# PowerSupply.net
KiCad netlist of a schematic drawn in Altium Designer
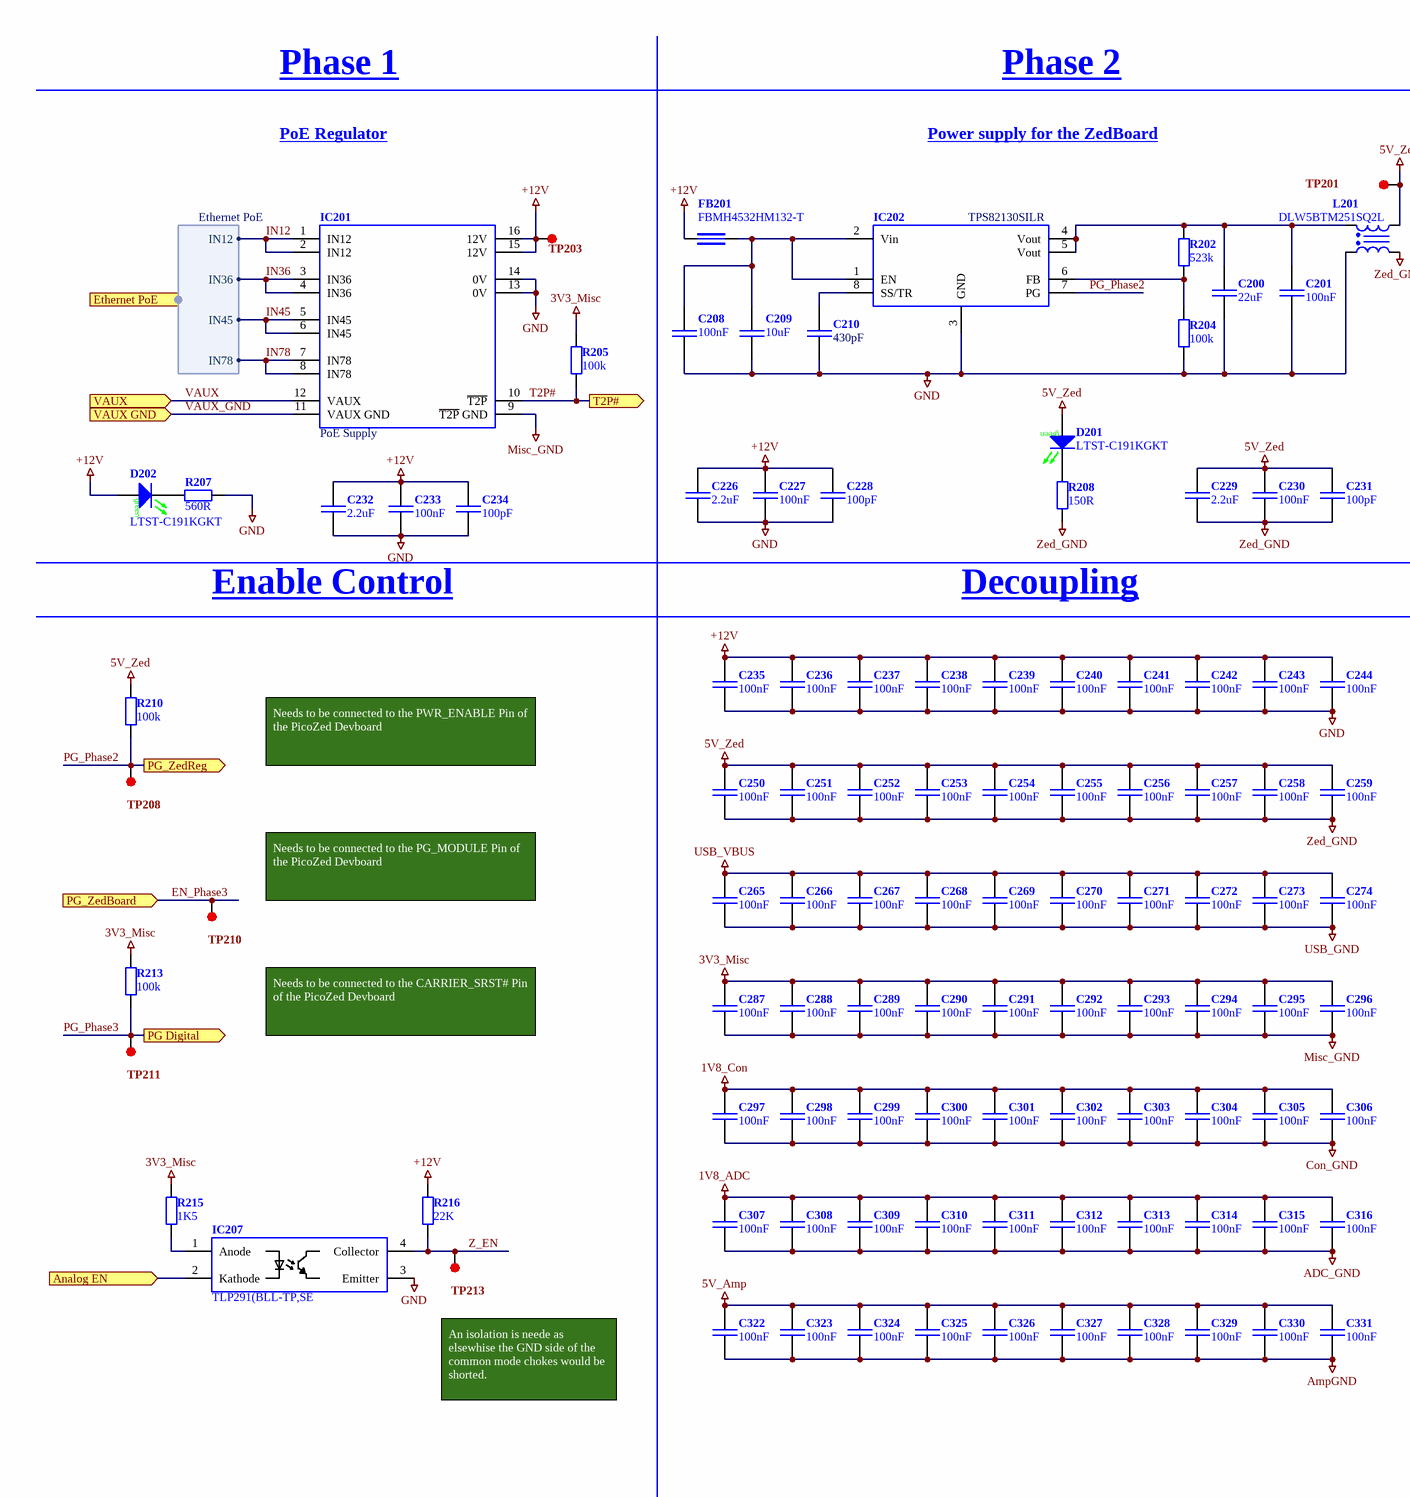
[diagram p0: PowerSupply.SchDoc, left]
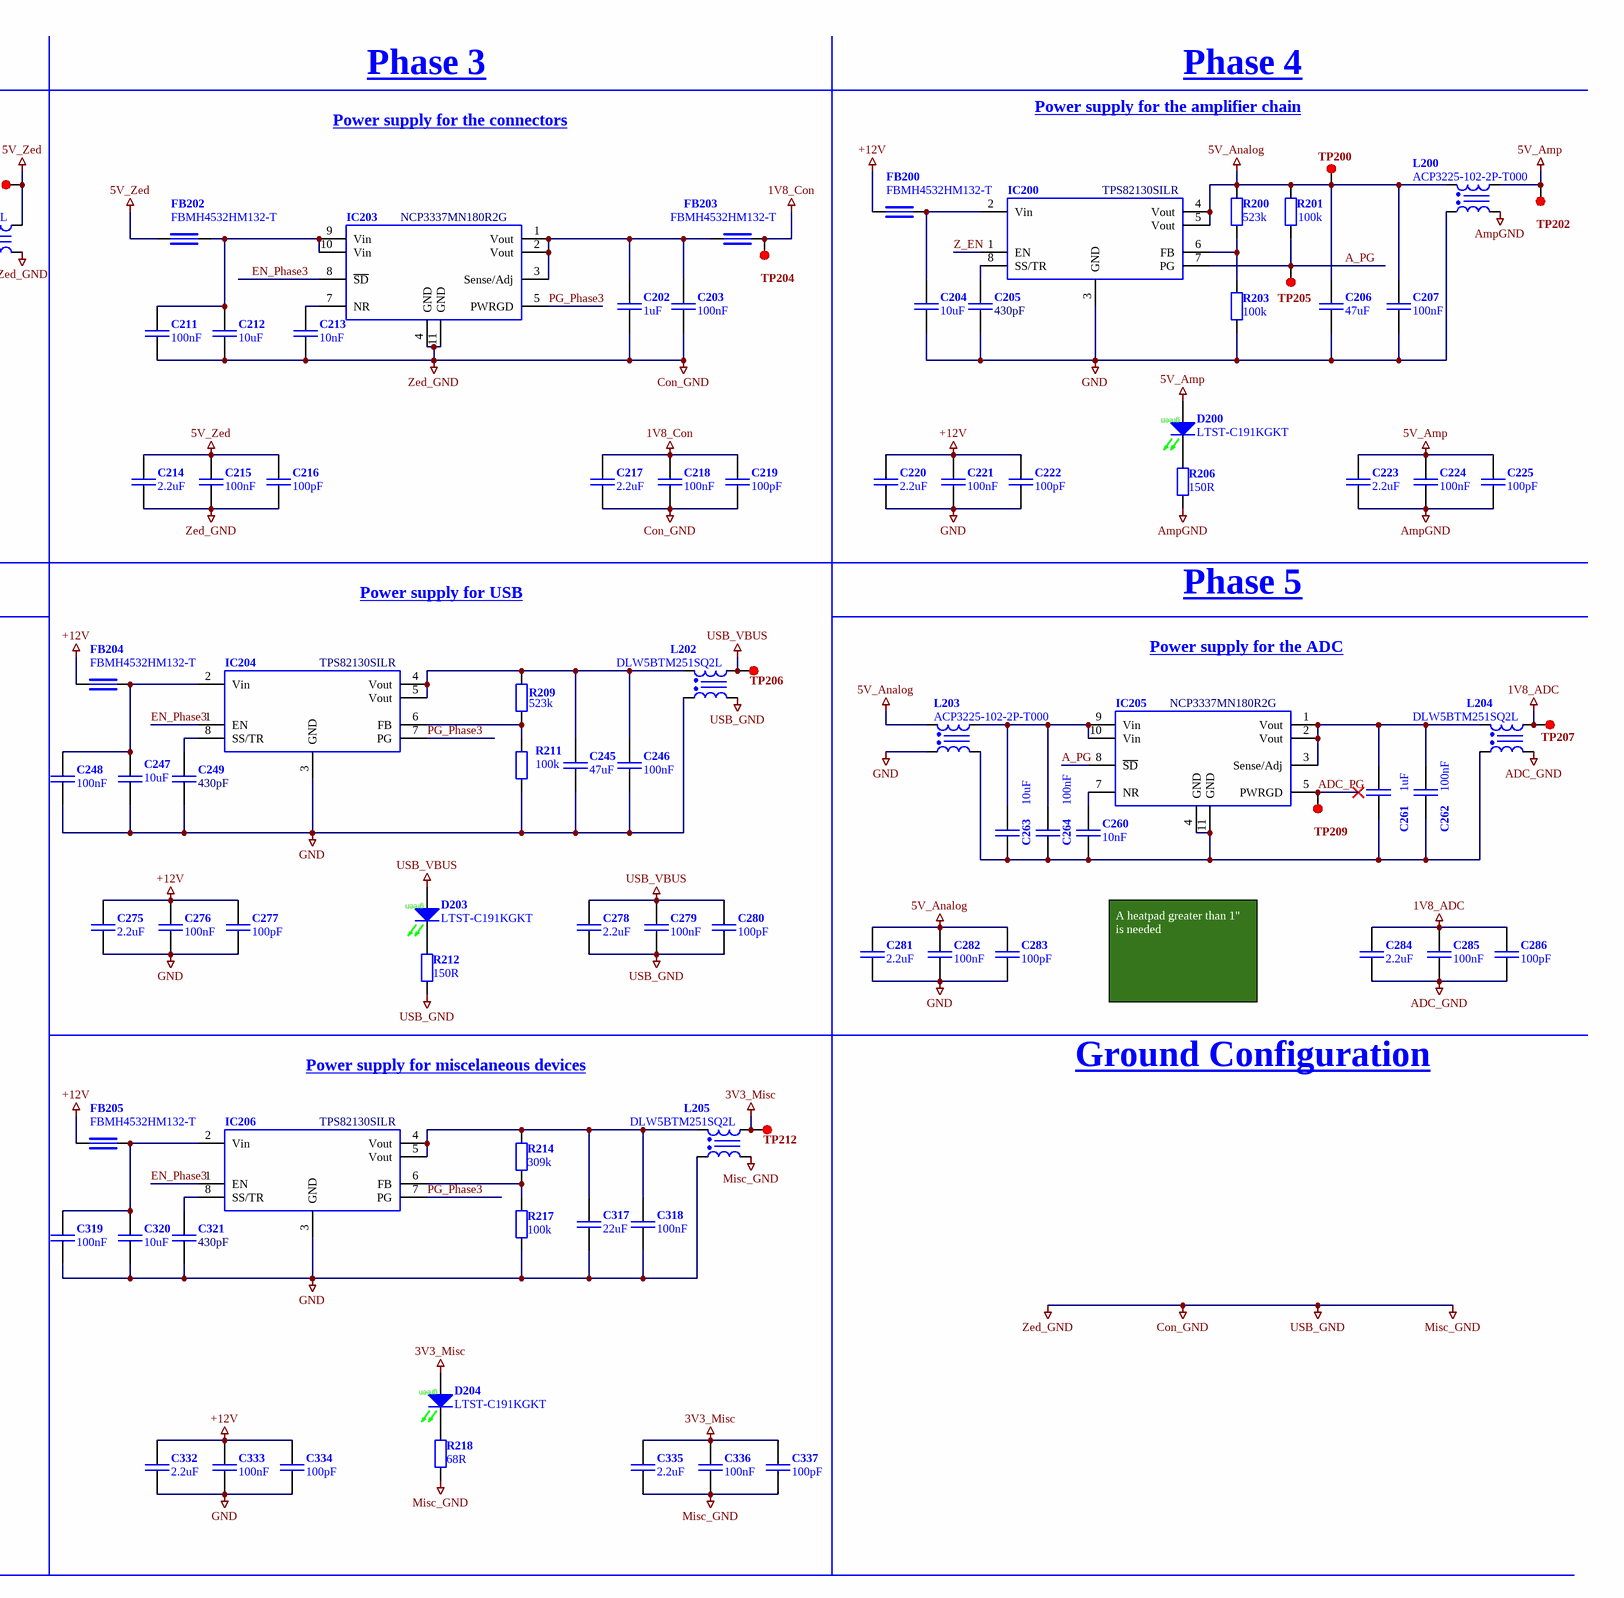
[diagram p1: PowerSupply.SchDoc, right]

(export (version "E")
  (design (tool "Eeschema 10.0.6"))
  (components
    (comp (ref "C200")
      (value "22uF")
      (footprint "PrometheusLib:C_0805_N [CAPC2013N IPC]")
      (libsource (lib "PrometheusLib") (part "C_GENERIC"))
    )
    (comp (ref "C201")
      (value "100nF")
      (footprint "PrometheusLib:C_0603_N [CAPC1608N IPC]")
      (libsource (lib "PrometheusLib") (part "C_GENERIC"))
    )
    (comp (ref "C202")
      (value "1uF")
      (footprint "PrometheusLib:C_0603_N [CAPC1608N IPC]")
      (libsource (lib "PrometheusLib") (part "C_GENERIC"))
    )
    (comp (ref "C203")
      (value "100nF")
      (footprint "PrometheusLib:C_0603_N [CAPC1608N IPC]")
      (libsource (lib "PrometheusLib") (part "C_GENERIC"))
    )
    (comp (ref "C204")
      (value "10uF")
      (footprint "PrometheusLib:C_1210_N [CAPC3225N IPC]")
      (libsource (lib "PrometheusLib") (part "C_GENERIC"))
    )
    (comp (ref "C205")
      (value "430pF")
      (footprint "PrometheusLib:C_0603_N [CAPC1608N IPC]")
      (libsource (lib "PrometheusLib") (part "C_GENERIC"))
    )
    (comp (ref "C206")
      (value "47uF")
      (footprint "PrometheusLib:C_0805_N [CAPC2013N IPC]")
      (libsource (lib "PrometheusLib") (part "C_GENERIC"))
    )
    (comp (ref "C207")
      (value "100nF")
      (footprint "PrometheusLib:C_0603_N [CAPC1608N IPC]")
      (libsource (lib "PrometheusLib") (part "C_GENERIC"))
    )
    (comp (ref "C208")
      (value "100nF")
      (footprint "PrometheusLib:C_0603_N [CAPC1608N IPC]")
      (libsource (lib "PrometheusLib") (part "C_GENERIC"))
    )
    (comp (ref "C209")
      (value "10uF")
      (footprint "PrometheusLib:C_1210_N [CAPC3225N IPC]")
      (libsource (lib "PrometheusLib") (part "C_GENERIC"))
    )
    (comp (ref "C210")
      (value "430pF")
      (footprint "PrometheusLib:C_0603_N [CAPC1608N IPC]")
      (libsource (lib "PrometheusLib") (part "C_GENERIC"))
    )
    (comp (ref "C211")
      (value "100nF")
      (footprint "PrometheusLib:C_0603_N [CAPC1608N IPC]")
      (libsource (lib "PrometheusLib") (part "C_GENERIC"))
    )
    (comp (ref "C212")
      (value "10uF")
      (footprint "PrometheusLib:C_0603_N [CAPC1608N IPC]")
      (libsource (lib "PrometheusLib") (part "C_GENERIC"))
    )
    (comp (ref "C213")
      (value "10nF")
      (footprint "PrometheusLib:C_0603_N [CAPC1608N IPC]")
      (libsource (lib "PrometheusLib") (part "C_GENERIC"))
    )
    (comp (ref "C214")
      (value "2.2uF")
      (footprint "PrometheusLib:C_1206_N [CAPC3216N IPC]")
      (libsource (lib "PrometheusLib") (part "C_GENERIC"))
    )
    (comp (ref "C215")
      (value "100nF")
      (footprint "PrometheusLib:C_0805_N [CAPC2013N IPC]")
      (libsource (lib "PrometheusLib") (part "C_GENERIC"))
    )
    (comp (ref "C216")
      (value "100pF")
      (footprint "PrometheusLib:C_0603_N [CAPC1608N IPC]")
      (libsource (lib "PrometheusLib") (part "C_GENERIC"))
    )
    (comp (ref "C217")
      (value "2.2uF")
      (footprint "PrometheusLib:C_1206_N [CAPC3216N IPC]")
      (libsource (lib "PrometheusLib") (part "C_GENERIC"))
    )
    (comp (ref "C218")
      (value "100nF")
      (footprint "PrometheusLib:C_0805_N [CAPC2013N IPC]")
      (libsource (lib "PrometheusLib") (part "C_GENERIC"))
    )
    (comp (ref "C219")
      (value "100pF")
      (footprint "PrometheusLib:C_0603_N [CAPC1608N IPC]")
      (libsource (lib "PrometheusLib") (part "C_GENERIC"))
    )
    (comp (ref "C220")
      (value "2.2uF")
      (footprint "PrometheusLib:C_1206_N [CAPC3216N IPC]")
      (libsource (lib "PrometheusLib") (part "C_GENERIC"))
    )
    (comp (ref "C221")
      (value "100nF")
      (footprint "PrometheusLib:C_0805_N [CAPC2013N IPC]")
      (libsource (lib "PrometheusLib") (part "C_GENERIC"))
    )
    (comp (ref "C222")
      (value "100pF")
      (footprint "PrometheusLib:C_0603_N [CAPC1608N IPC]")
      (libsource (lib "PrometheusLib") (part "C_GENERIC"))
    )
    (comp (ref "C223")
      (value "2.2uF")
      (footprint "PrometheusLib:C_1206_N [CAPC3216N IPC]")
      (libsource (lib "PrometheusLib") (part "C_GENERIC"))
    )
    (comp (ref "C224")
      (value "100nF")
      (footprint "PrometheusLib:C_0805_N [CAPC2013N IPC]")
      (libsource (lib "PrometheusLib") (part "C_GENERIC"))
    )
    (comp (ref "C225")
      (value "100pF")
      (footprint "PrometheusLib:C_0603_N [CAPC1608N IPC]")
      (libsource (lib "PrometheusLib") (part "C_GENERIC"))
    )
    (comp (ref "C226")
      (value "2.2uF")
      (footprint "PrometheusLib:C_1206_N [CAPC3216N IPC]")
      (libsource (lib "PrometheusLib") (part "C_GENERIC"))
    )
    (comp (ref "C227")
      (value "100nF")
      (footprint "PrometheusLib:C_0805_N [CAPC2013N IPC]")
      (libsource (lib "PrometheusLib") (part "C_GENERIC"))
    )
    (comp (ref "C228")
      (value "100pF")
      (footprint "PrometheusLib:C_0603_N [CAPC1608N IPC]")
      (libsource (lib "PrometheusLib") (part "C_GENERIC"))
    )
    (comp (ref "C229")
      (value "2.2uF")
      (footprint "PrometheusLib:C_1206_N [CAPC3216N IPC]")
      (libsource (lib "PrometheusLib") (part "C_GENERIC"))
    )
    (comp (ref "C230")
      (value "100nF")
      (footprint "PrometheusLib:C_0805_N [CAPC2013N IPC]")
      (libsource (lib "PrometheusLib") (part "C_GENERIC"))
    )
    (comp (ref "C231")
      (value "100pF")
      (footprint "PrometheusLib:C_0603_N [CAPC1608N IPC]")
      (libsource (lib "PrometheusLib") (part "C_GENERIC"))
    )
    (comp (ref "C232")
      (value "2.2uF")
      (footprint "PrometheusLib:C_1206_N [CAPC3216N IPC]")
      (libsource (lib "PrometheusLib") (part "C_GENERIC"))
    )
    (comp (ref "C233")
      (value "100nF")
      (footprint "PrometheusLib:C_0805_N [CAPC2013N IPC]")
      (libsource (lib "PrometheusLib") (part "C_GENERIC"))
    )
    (comp (ref "C234")
      (value "100pF")
      (footprint "PrometheusLib:C_0603_N [CAPC1608N IPC]")
      (libsource (lib "PrometheusLib") (part "C_GENERIC"))
    )
    (comp (ref "C235")
      (value "100nF")
      (footprint "PrometheusLib:C_0603_N [CAPC1608N IPC]")
      (libsource (lib "PrometheusLib") (part "C_GENERIC"))
    )
    (comp (ref "C236")
      (value "100nF")
      (footprint "PrometheusLib:C_0603_N [CAPC1608N IPC]")
      (libsource (lib "PrometheusLib") (part "C_GENERIC"))
    )
    (comp (ref "C237")
      (value "100nF")
      (footprint "PrometheusLib:C_0603_N [CAPC1608N IPC]")
      (libsource (lib "PrometheusLib") (part "C_GENERIC"))
    )
    (comp (ref "C238")
      (value "100nF")
      (footprint "PrometheusLib:C_0603_N [CAPC1608N IPC]")
      (libsource (lib "PrometheusLib") (part "C_GENERIC"))
    )
    (comp (ref "C239")
      (value "100nF")
      (footprint "PrometheusLib:C_0603_N [CAPC1608N IPC]")
      (libsource (lib "PrometheusLib") (part "C_GENERIC"))
    )
    (comp (ref "C240")
      (value "100nF")
      (footprint "PrometheusLib:C_0603_N [CAPC1608N IPC]")
      (libsource (lib "PrometheusLib") (part "C_GENERIC"))
    )
    (comp (ref "C241")
      (value "100nF")
      (footprint "PrometheusLib:C_0603_N [CAPC1608N IPC]")
      (libsource (lib "PrometheusLib") (part "C_GENERIC"))
    )
    (comp (ref "C242")
      (value "100nF")
      (footprint "PrometheusLib:C_0603_N [CAPC1608N IPC]")
      (libsource (lib "PrometheusLib") (part "C_GENERIC"))
    )
    (comp (ref "C243")
      (value "100nF")
      (footprint "PrometheusLib:C_0603_N [CAPC1608N IPC]")
      (libsource (lib "PrometheusLib") (part "C_GENERIC"))
    )
    (comp (ref "C244")
      (value "100nF")
      (footprint "PrometheusLib:C_0603_N [CAPC1608N IPC]")
      (libsource (lib "PrometheusLib") (part "C_GENERIC"))
    )
    (comp (ref "C245")
      (value "47uF")
      (footprint "PrometheusLib:C_0603_N [CAPC1608N IPC]")
      (libsource (lib "PrometheusLib") (part "C_GENERIC"))
    )
    (comp (ref "C246")
      (value "100nF")
      (footprint "PrometheusLib:C_0603_N [CAPC1608N IPC]")
      (libsource (lib "PrometheusLib") (part "C_GENERIC"))
    )
    (comp (ref "C247")
      (value "10uF")
      (footprint "PrometheusLib:C_1210_N [CAPC3225N IPC]")
      (libsource (lib "PrometheusLib") (part "C_GENERIC"))
    )
    (comp (ref "C248")
      (value "100nF")
      (footprint "PrometheusLib:C_0603_N [CAPC1608N IPC]")
      (libsource (lib "PrometheusLib") (part "C_GENERIC"))
    )
    (comp (ref "C249")
      (value "430pF")
      (footprint "PrometheusLib:C_0603_N [CAPC1608N IPC]")
      (libsource (lib "PrometheusLib") (part "C_GENERIC"))
    )
    (comp (ref "C250")
      (value "100nF")
      (footprint "PrometheusLib:C_0603_N [CAPC1608N IPC]")
      (libsource (lib "PrometheusLib") (part "C_GENERIC"))
    )
    (comp (ref "C251")
      (value "100nF")
      (footprint "PrometheusLib:C_0603_N [CAPC1608N IPC]")
      (libsource (lib "PrometheusLib") (part "C_GENERIC"))
    )
    (comp (ref "C252")
      (value "100nF")
      (footprint "PrometheusLib:C_0603_N [CAPC1608N IPC]")
      (libsource (lib "PrometheusLib") (part "C_GENERIC"))
    )
    (comp (ref "C253")
      (value "100nF")
      (footprint "PrometheusLib:C_0603_N [CAPC1608N IPC]")
      (libsource (lib "PrometheusLib") (part "C_GENERIC"))
    )
    (comp (ref "C254")
      (value "100nF")
      (footprint "PrometheusLib:C_0603_N [CAPC1608N IPC]")
      (libsource (lib "PrometheusLib") (part "C_GENERIC"))
    )
    (comp (ref "C255")
      (value "100nF")
      (footprint "PrometheusLib:C_0603_N [CAPC1608N IPC]")
      (libsource (lib "PrometheusLib") (part "C_GENERIC"))
    )
    (comp (ref "C256")
      (value "100nF")
      (footprint "PrometheusLib:C_0603_N [CAPC1608N IPC]")
      (libsource (lib "PrometheusLib") (part "C_GENERIC"))
    )
    (comp (ref "C257")
      (value "100nF")
      (footprint "PrometheusLib:C_0603_N [CAPC1608N IPC]")
      (libsource (lib "PrometheusLib") (part "C_GENERIC"))
    )
    (comp (ref "C258")
      (value "100nF")
      (footprint "PrometheusLib:C_0603_N [CAPC1608N IPC]")
      (libsource (lib "PrometheusLib") (part "C_GENERIC"))
    )
    (comp (ref "C259")
      (value "100nF")
      (footprint "PrometheusLib:C_0603_N [CAPC1608N IPC]")
      (libsource (lib "PrometheusLib") (part "C_GENERIC"))
    )
    (comp (ref "C260")
      (value "10nF")
      (footprint "PrometheusLib:C_0603_N [CAPC1608N IPC]")
      (libsource (lib "PrometheusLib") (part "C_GENERIC"))
    )
    (comp (ref "C261")
      (value "1uF")
      (footprint "PrometheusLib:C_0603_N [CAPC1608N IPC]")
      (libsource (lib "PrometheusLib") (part "C_GENERIC"))
    )
    (comp (ref "C262")
      (value "100nF")
      (footprint "PrometheusLib:C_0603_N [CAPC1608N IPC]")
      (libsource (lib "PrometheusLib") (part "C_GENERIC"))
    )
    (comp (ref "C263")
      (value "10uF")
      (footprint "PrometheusLib:C_0603_N [CAPC1608N IPC]")
      (libsource (lib "PrometheusLib") (part "C_GENERIC"))
    )
    (comp (ref "C264")
      (value "100nF")
      (footprint "PrometheusLib:C_0603_N [CAPC1608N IPC]")
      (libsource (lib "PrometheusLib") (part "C_GENERIC"))
    )
    (comp (ref "C265")
      (value "100nF")
      (footprint "PrometheusLib:C_0603_N [CAPC1608N IPC]")
      (libsource (lib "PrometheusLib") (part "C_GENERIC"))
    )
    (comp (ref "C266")
      (value "100nF")
      (footprint "PrometheusLib:C_0603_N [CAPC1608N IPC]")
      (libsource (lib "PrometheusLib") (part "C_GENERIC"))
    )
    (comp (ref "C267")
      (value "100nF")
      (footprint "PrometheusLib:C_0603_N [CAPC1608N IPC]")
      (libsource (lib "PrometheusLib") (part "C_GENERIC"))
    )
    (comp (ref "C268")
      (value "100nF")
      (footprint "PrometheusLib:C_0603_N [CAPC1608N IPC]")
      (libsource (lib "PrometheusLib") (part "C_GENERIC"))
    )
    (comp (ref "C269")
      (value "100nF")
      (footprint "PrometheusLib:C_0603_N [CAPC1608N IPC]")
      (libsource (lib "PrometheusLib") (part "C_GENERIC"))
    )
    (comp (ref "C270")
      (value "100nF")
      (footprint "PrometheusLib:C_0603_N [CAPC1608N IPC]")
      (libsource (lib "PrometheusLib") (part "C_GENERIC"))
    )
    (comp (ref "C271")
      (value "100nF")
      (footprint "PrometheusLib:C_0603_N [CAPC1608N IPC]")
      (libsource (lib "PrometheusLib") (part "C_GENERIC"))
    )
    (comp (ref "C272")
      (value "100nF")
      (footprint "PrometheusLib:C_0603_N [CAPC1608N IPC]")
      (libsource (lib "PrometheusLib") (part "C_GENERIC"))
    )
    (comp (ref "C273")
      (value "100nF")
      (footprint "PrometheusLib:C_0603_N [CAPC1608N IPC]")
      (libsource (lib "PrometheusLib") (part "C_GENERIC"))
    )
    (comp (ref "C274")
      (value "100nF")
      (footprint "PrometheusLib:C_0603_N [CAPC1608N IPC]")
      (libsource (lib "PrometheusLib") (part "C_GENERIC"))
    )
    (comp (ref "C275")
      (value "2.2uF")
      (footprint "PrometheusLib:C_1206_N [CAPC3216N IPC]")
      (libsource (lib "PrometheusLib") (part "C_GENERIC"))
    )
    (comp (ref "C276")
      (value "100nF")
      (footprint "PrometheusLib:C_0805_N [CAPC2013N IPC]")
      (libsource (lib "PrometheusLib") (part "C_GENERIC"))
    )
    (comp (ref "C277")
      (value "100pF")
      (footprint "PrometheusLib:C_0603_N [CAPC1608N IPC]")
      (libsource (lib "PrometheusLib") (part "C_GENERIC"))
    )
    (comp (ref "C278")
      (value "2.2uF")
      (footprint "PrometheusLib:C_1206_N [CAPC3216N IPC]")
      (libsource (lib "PrometheusLib") (part "C_GENERIC"))
    )
    (comp (ref "C279")
      (value "100nF")
      (footprint "PrometheusLib:C_0805_N [CAPC2013N IPC]")
      (libsource (lib "PrometheusLib") (part "C_GENERIC"))
    )
    (comp (ref "C280")
      (value "100pF")
      (footprint "PrometheusLib:C_0603_N [CAPC1608N IPC]")
      (libsource (lib "PrometheusLib") (part "C_GENERIC"))
    )
    (comp (ref "C281")
      (value "2.2uF")
      (footprint "PrometheusLib:C_1206_N [CAPC3216N IPC]")
      (libsource (lib "PrometheusLib") (part "C_GENERIC"))
    )
    (comp (ref "C282")
      (value "100nF")
      (footprint "PrometheusLib:C_0805_N [CAPC2013N IPC]")
      (libsource (lib "PrometheusLib") (part "C_GENERIC"))
    )
    (comp (ref "C283")
      (value "100pF")
      (footprint "PrometheusLib:C_0603_N [CAPC1608N IPC]")
      (libsource (lib "PrometheusLib") (part "C_GENERIC"))
    )
    (comp (ref "C284")
      (value "2.2uF")
      (footprint "PrometheusLib:C_1206_N [CAPC3216N IPC]")
      (libsource (lib "PrometheusLib") (part "C_GENERIC"))
    )
    (comp (ref "C285")
      (value "100nF")
      (footprint "PrometheusLib:C_0805_N [CAPC2013N IPC]")
      (libsource (lib "PrometheusLib") (part "C_GENERIC"))
    )
    (comp (ref "C286")
      (value "100pF")
      (footprint "PrometheusLib:C_0603_N [CAPC1608N IPC]")
      (libsource (lib "PrometheusLib") (part "C_GENERIC"))
    )
    (comp (ref "C287")
      (value "100nF")
      (footprint "PrometheusLib:C_0603_N [CAPC1608N IPC]")
      (libsource (lib "PrometheusLib") (part "C_GENERIC"))
    )
    (comp (ref "C288")
      (value "100nF")
      (footprint "PrometheusLib:C_0603_N [CAPC1608N IPC]")
      (libsource (lib "PrometheusLib") (part "C_GENERIC"))
    )
    (comp (ref "C289")
      (value "100nF")
      (footprint "PrometheusLib:C_0603_N [CAPC1608N IPC]")
      (libsource (lib "PrometheusLib") (part "C_GENERIC"))
    )
    (comp (ref "C290")
      (value "100nF")
      (footprint "PrometheusLib:C_0603_N [CAPC1608N IPC]")
      (libsource (lib "PrometheusLib") (part "C_GENERIC"))
    )
    (comp (ref "C291")
      (value "100nF")
      (footprint "PrometheusLib:C_0603_N [CAPC1608N IPC]")
      (libsource (lib "PrometheusLib") (part "C_GENERIC"))
    )
    (comp (ref "C292")
      (value "100nF")
      (footprint "PrometheusLib:C_0603_N [CAPC1608N IPC]")
      (libsource (lib "PrometheusLib") (part "C_GENERIC"))
    )
    (comp (ref "C293")
      (value "100nF")
      (footprint "PrometheusLib:C_0603_N [CAPC1608N IPC]")
      (libsource (lib "PrometheusLib") (part "C_GENERIC"))
    )
    (comp (ref "C294")
      (value "100nF")
      (footprint "PrometheusLib:C_0603_N [CAPC1608N IPC]")
      (libsource (lib "PrometheusLib") (part "C_GENERIC"))
    )
    (comp (ref "C295")
      (value "100nF")
      (footprint "PrometheusLib:C_0603_N [CAPC1608N IPC]")
      (libsource (lib "PrometheusLib") (part "C_GENERIC"))
    )
    (comp (ref "C296")
      (value "100nF")
      (footprint "PrometheusLib:C_0603_N [CAPC1608N IPC]")
      (libsource (lib "PrometheusLib") (part "C_GENERIC"))
    )
    (comp (ref "C297")
      (value "100nF")
      (footprint "PrometheusLib:C_0603_N [CAPC1608N IPC]")
      (libsource (lib "PrometheusLib") (part "C_GENERIC"))
    )
    (comp (ref "C298")
      (value "100nF")
      (footprint "PrometheusLib:C_0603_N [CAPC1608N IPC]")
      (libsource (lib "PrometheusLib") (part "C_GENERIC"))
    )
    (comp (ref "C299")
      (value "100nF")
      (footprint "PrometheusLib:C_0603_N [CAPC1608N IPC]")
      (libsource (lib "PrometheusLib") (part "C_GENERIC"))
    )
    (comp (ref "C300")
      (value "100nF")
      (footprint "PrometheusLib:C_0603_N [CAPC1608N IPC]")
      (libsource (lib "PrometheusLib") (part "C_GENERIC"))
    )
    (comp (ref "C301")
      (value "100nF")
      (footprint "PrometheusLib:C_0603_N [CAPC1608N IPC]")
      (libsource (lib "PrometheusLib") (part "C_GENERIC"))
    )
    (comp (ref "C302")
      (value "100nF")
      (footprint "PrometheusLib:C_0603_N [CAPC1608N IPC]")
      (libsource (lib "PrometheusLib") (part "C_GENERIC"))
    )
    (comp (ref "C303")
      (value "100nF")
      (footprint "PrometheusLib:C_0603_N [CAPC1608N IPC]")
      (libsource (lib "PrometheusLib") (part "C_GENERIC"))
    )
    (comp (ref "C304")
      (value "100nF")
      (footprint "PrometheusLib:C_0603_N [CAPC1608N IPC]")
      (libsource (lib "PrometheusLib") (part "C_GENERIC"))
    )
    (comp (ref "C305")
      (value "100nF")
      (footprint "PrometheusLib:C_0603_N [CAPC1608N IPC]")
      (libsource (lib "PrometheusLib") (part "C_GENERIC"))
    )
    (comp (ref "C306")
      (value "100nF")
      (footprint "PrometheusLib:C_0603_N [CAPC1608N IPC]")
      (libsource (lib "PrometheusLib") (part "C_GENERIC"))
    )
    (comp (ref "C307")
      (value "100nF")
      (footprint "PrometheusLib:C_0603_N [CAPC1608N IPC]")
      (libsource (lib "PrometheusLib") (part "C_GENERIC"))
    )
    (comp (ref "C308")
      (value "100nF")
      (footprint "PrometheusLib:C_0603_N [CAPC1608N IPC]")
      (libsource (lib "PrometheusLib") (part "C_GENERIC"))
    )
    (comp (ref "C309")
      (value "100nF")
      (footprint "PrometheusLib:C_0603_N [CAPC1608N IPC]")
      (libsource (lib "PrometheusLib") (part "C_GENERIC"))
    )
    (comp (ref "C310")
      (value "100nF")
      (footprint "PrometheusLib:C_0603_N [CAPC1608N IPC]")
      (libsource (lib "PrometheusLib") (part "C_GENERIC"))
    )
    (comp (ref "C311")
      (value "100nF")
      (footprint "PrometheusLib:C_0603_N [CAPC1608N IPC]")
      (libsource (lib "PrometheusLib") (part "C_GENERIC"))
    )
    (comp (ref "C312")
      (value "100nF")
      (footprint "PrometheusLib:C_0603_N [CAPC1608N IPC]")
      (libsource (lib "PrometheusLib") (part "C_GENERIC"))
    )
    (comp (ref "C313")
      (value "100nF")
      (footprint "PrometheusLib:C_0603_N [CAPC1608N IPC]")
      (libsource (lib "PrometheusLib") (part "C_GENERIC"))
    )
    (comp (ref "C314")
      (value "100nF")
      (footprint "PrometheusLib:C_0603_N [CAPC1608N IPC]")
      (libsource (lib "PrometheusLib") (part "C_GENERIC"))
    )
    (comp (ref "C315")
      (value "100nF")
      (footprint "PrometheusLib:C_0603_N [CAPC1608N IPC]")
      (libsource (lib "PrometheusLib") (part "C_GENERIC"))
    )
    (comp (ref "C316")
      (value "100nF")
      (footprint "PrometheusLib:C_0603_N [CAPC1608N IPC]")
      (libsource (lib "PrometheusLib") (part "C_GENERIC"))
    )
    (comp (ref "C317")
      (value "22uF")
      (footprint "PrometheusLib:C_0805_N [CAPC2013N IPC]")
      (libsource (lib "PrometheusLib") (part "C_GENERIC"))
    )
    (comp (ref "C318")
      (value "100nF")
      (footprint "PrometheusLib:C_0603_N [CAPC1608N IPC]")
      (libsource (lib "PrometheusLib") (part "C_GENERIC"))
    )
    (comp (ref "C319")
      (value "100nF")
      (footprint "PrometheusLib:C_0603_N [CAPC1608N IPC]")
      (libsource (lib "PrometheusLib") (part "C_GENERIC"))
    )
    (comp (ref "C320")
      (value "10uF")
      (footprint "PrometheusLib:C_1210_N [CAPC3225N IPC]")
      (libsource (lib "PrometheusLib") (part "C_GENERIC"))
    )
    (comp (ref "C321")
      (value "430pF")
      (footprint "PrometheusLib:C_0603_N [CAPC1608N IPC]")
      (libsource (lib "PrometheusLib") (part "C_GENERIC"))
    )
    (comp (ref "C322")
      (value "100nF")
      (footprint "PrometheusLib:C_0603_N [CAPC1608N IPC]")
      (libsource (lib "PrometheusLib") (part "C_GENERIC"))
    )
    (comp (ref "C323")
      (value "100nF")
      (footprint "PrometheusLib:C_0603_N [CAPC1608N IPC]")
      (libsource (lib "PrometheusLib") (part "C_GENERIC"))
    )
    (comp (ref "C324")
      (value "100nF")
      (footprint "PrometheusLib:C_0603_N [CAPC1608N IPC]")
      (libsource (lib "PrometheusLib") (part "C_GENERIC"))
    )
    (comp (ref "C325")
      (value "100nF")
      (footprint "PrometheusLib:C_0603_N [CAPC1608N IPC]")
      (libsource (lib "PrometheusLib") (part "C_GENERIC"))
    )
    (comp (ref "C326")
      (value "100nF")
      (footprint "PrometheusLib:C_0603_N [CAPC1608N IPC]")
      (libsource (lib "PrometheusLib") (part "C_GENERIC"))
    )
    (comp (ref "C327")
      (value "100nF")
      (footprint "PrometheusLib:C_0603_N [CAPC1608N IPC]")
      (libsource (lib "PrometheusLib") (part "C_GENERIC"))
    )
    (comp (ref "C328")
      (value "100nF")
      (footprint "PrometheusLib:C_0603_N [CAPC1608N IPC]")
      (libsource (lib "PrometheusLib") (part "C_GENERIC"))
    )
    (comp (ref "C329")
      (value "100nF")
      (footprint "PrometheusLib:C_0603_N [CAPC1608N IPC]")
      (libsource (lib "PrometheusLib") (part "C_GENERIC"))
    )
    (comp (ref "C330")
      (value "100nF")
      (footprint "PrometheusLib:C_0603_N [CAPC1608N IPC]")
      (libsource (lib "PrometheusLib") (part "C_GENERIC"))
    )
    (comp (ref "C331")
      (value "100nF")
      (footprint "PrometheusLib:C_0603_N [CAPC1608N IPC]")
      (libsource (lib "PrometheusLib") (part "C_GENERIC"))
    )
    (comp (ref "C332")
      (value "2.2uF")
      (footprint "PrometheusLib:C_1206_N [CAPC3216N IPC]")
      (libsource (lib "PrometheusLib") (part "C_GENERIC"))
    )
    (comp (ref "C333")
      (value "100nF")
      (footprint "PrometheusLib:C_0805_N [CAPC2013N IPC]")
      (libsource (lib "PrometheusLib") (part "C_GENERIC"))
    )
    (comp (ref "C334")
      (value "100pF")
      (footprint "PrometheusLib:C_0603_N [CAPC1608N IPC]")
      (libsource (lib "PrometheusLib") (part "C_GENERIC"))
    )
    (comp (ref "C335")
      (value "2.2uF")
      (footprint "PrometheusLib:C_1206_N [CAPC3216N IPC]")
      (libsource (lib "PrometheusLib") (part "C_GENERIC"))
    )
    (comp (ref "C336")
      (value "100nF")
      (footprint "PrometheusLib:C_0805_N [CAPC2013N IPC]")
      (libsource (lib "PrometheusLib") (part "C_GENERIC"))
    )
    (comp (ref "C337")
      (value "100pF")
      (footprint "PrometheusLib:C_0603_N [CAPC1608N IPC]")
      (libsource (lib "PrometheusLib") (part "C_GENERIC"))
    )
    (comp (ref "D200")
      (value "LTST-C191KGKT")
      (footprint "PrometheusLib:LED_0603-GREEN_N_AK")
      (libsource (lib "PrometheusLib") (part "LED_GREEN_GENERIC"))
    )
    (comp (ref "D201")
      (value "LTST-C191KGKT")
      (footprint "PrometheusLib:LED_0603-GREEN_N_AK")
      (libsource (lib "PrometheusLib") (part "LED_GREEN_GENERIC"))
    )
    (comp (ref "D202")
      (value "LTST-C191KGKT")
      (footprint "PrometheusLib:LED_0603-GREEN_N_AK")
      (libsource (lib "PrometheusLib") (part "LED_GREEN_GENERIC"))
    )
    (comp (ref "D203")
      (value "LTST-C191KGKT")
      (footprint "PrometheusLib:LED_0603-GREEN_N_AK")
      (libsource (lib "PrometheusLib") (part "LED_GREEN_GENERIC"))
    )
    (comp (ref "D204")
      (value "LTST-C191KGKT")
      (footprint "PrometheusLib:LED_0603-GREEN_N_AK")
      (libsource (lib "PrometheusLib") (part "LED_GREEN_GENERIC"))
    )
    (comp (ref "FB200")
      (value "FBMH4532HM132-T")
      (footprint "L_1812_N [INDC4532X25N IPC]")
      (description "1,3 kOHM @ 100 MHz\r\n3 A\r\n60 mOHM")
      (libsource (lib "PrometheusLib") (part "FB_FBMH4532HM132-T"))
    )
    (comp (ref "FB201")
      (value "FBMH4532HM132-T")
      (footprint "L_1812_N [INDC4532X25N IPC]")
      (description "1,3 kOHM @ 100 MHz\r\n3 A\r\n60 mOHM")
      (libsource (lib "PrometheusLib") (part "FB_FBMH4532HM132-T"))
    )
    (comp (ref "FB202")
      (value "FBMH4532HM132-T")
      (footprint "L_1812_N [INDC4532X25N IPC]")
      (description "1,3 kOHM @ 100 MHz\r\n3 A\r\n60 mOHM")
      (libsource (lib "PrometheusLib") (part "FB_FBMH4532HM132-T"))
    )
    (comp (ref "FB203")
      (value "FBMH4532HM132-T")
      (footprint "L_1812_N [INDC4532X25N IPC]")
      (description "1,3 kOHM @ 100 MHz\r\n3 A\r\n60 mOHM")
      (libsource (lib "PrometheusLib") (part "FB_FBMH4532HM132-T"))
    )
    (comp (ref "FB204")
      (value "FBMH4532HM132-T")
      (footprint "L_1812_N [INDC4532X25N IPC]")
      (description "1,3 kOHM @ 100 MHz\r\n3 A\r\n60 mOHM")
      (libsource (lib "PrometheusLib") (part "FB_FBMH4532HM132-T"))
    )
    (comp (ref "FB205")
      (value "FBMH4532HM132-T")
      (footprint "L_1812_N [INDC4532X25N IPC]")
      (description "1,3 kOHM @ 100 MHz\r\n3 A\r\n60 mOHM")
      (libsource (lib "PrometheusLib") (part "FB_FBMH4532HM132-T"))
    )
    (comp (ref "IC200")
      (value "TPS82130SILR")
      (footprint "SIL0008D")
      (description "Step-Down DC/DC\r\nVin = 4 V to 17 V\r\nVout = 0.9 V to 6 V Adjustable\r\nIout = 3 A")
      (libsource (lib "PrometheusLib") (part "SREG_TPS82130SILR"))
    )
    (comp (ref "IC201")
      (value "PoE Supply")
      (footprint "SREG_PoE_PowerSupply Prometheus")
      (libsource (lib "PrometheusLib") (part "SREG_PoE_PowerSupply"))
    )
    (comp (ref "IC202")
      (value "TPS82130SILR")
      (footprint "SIL0008D")
      (description "Step-Down DC/DC\r\nVin = 4 V to 17 V\r\nVout = 0.9 V to 6 V Adjustable\r\nIout = 3 A")
      (libsource (lib "PrometheusLib") (part "SREG_TPS82130SILR"))
    )
    (comp (ref "IC203")
      (value "NCP3337MN180R2G")
      (footprint "SON50P300X100_HS-11N")
      (description "LDO\r\nVin max. 16 V\r\nVout 1V8")
      (libsource (lib "PrometheusLib") (part "LDO_NCP3337"))
    )
    (comp (ref "IC204")
      (value "TPS82130SILR")
      (footprint "SIL0008D")
      (description "Step-Down DC/DC\r\nVin = 4 V to 17 V\r\nVout = 0.9 V to 6 V Adjustable\r\nIout = 3 A")
      (libsource (lib "PrometheusLib") (part "SREG_TPS82130SILR"))
    )
    (comp (ref "IC205")
      (value "NCP3337MN180R2G")
      (footprint "SON50P300X100_HS-11N")
      (description "LDO\r\nVin max. 16 V\r\nVout 1V8")
      (libsource (lib "PrometheusLib") (part "LDO_NCP3337"))
    )
    (comp (ref "IC206")
      (value "TPS82130SILR")
      (footprint "SIL0008D")
      (description "Step-Down DC/DC\r\nVin = 4 V to 17 V\r\nVout = 0.9 V to 6 V Adjustable\r\nIout = 3 A")
      (libsource (lib "PrometheusLib") (part "SREG_TPS82130SILR"))
    )
    (comp (ref "IC207")
      (value "TLP291(BLL-TP,SE")
      (footprint "SOP127P700X220-4N")
      (description "Opto-Isolator\r\nmin. VCE = 80 V\r\nmin. Current Transfer Ratio = 200 % @ 5 mA")
      (libsource (lib "PrometheusLib") (part "IC_TLP291(BLL-TP,SE"))
    )
    (comp (ref "L200")
      (value "ACP3225-102-2P-T000")
      (footprint "L_ACP3225-102-2P-T000")
      (libsource (lib "PrometheusLib") (part "L_COMMONMODE_CHOKE_744282010_1"))
    )
    (comp (ref "L201")
      (value "DLW5BTM251SQ2L")
      (footprint "L_COMMON_DLW5BTM251SQ2L Prometheus")
      (description "250 OHM @ 100 MHz\r\nI max. 5A\r\nDCR max. 20 mOHM\r\nVDC max. 50 V")
      (libsource (lib "PrometheusLib") (part "L_COMMONMODE_CHOKE_DLW5BTM251SQ2L"))
    )
    (comp (ref "L202")
      (value "DLW5BTM251SQ2L")
      (footprint "L_COMMON_DLW5BTM251SQ2L Prometheus")
      (description "250 OHM @ 100 MHz\r\nI max. 5A\r\nDCR max. 20 mOHM\r\nVDC max. 50 V")
      (libsource (lib "PrometheusLib") (part "L_COMMONMODE_CHOKE_DLW5BTM251SQ2L"))
    )
    (comp (ref "L203")
      (value "ACP3225-102-2P-T000")
      (footprint "L_ACP3225-102-2P-T000")
      (libsource (lib "PrometheusLib") (part "L_COMMONMODE_CHOKE_744282010_1"))
    )
    (comp (ref "L204")
      (value "DLW5BTM251SQ2L")
      (footprint "L_COMMON_DLW5BTM251SQ2L Prometheus")
      (description "250 OHM @ 100 MHz\r\nI max. 5A\r\nDCR max. 20 mOHM\r\nVDC max. 50 V")
      (libsource (lib "PrometheusLib") (part "L_COMMONMODE_CHOKE_DLW5BTM251SQ2L"))
    )
    (comp (ref "L205")
      (value "DLW5BTM251SQ2L")
      (footprint "L_COMMON_DLW5BTM251SQ2L Prometheus")
      (description "250 OHM @ 100 MHz\r\nI max. 5A\r\nDCR max. 20 mOHM\r\nVDC max. 50 V")
      (libsource (lib "PrometheusLib") (part "L_COMMONMODE_CHOKE_DLW5BTM251SQ2L"))
    )
    (comp (ref "R200")
      (value "523k")
      (footprint "PrometheusLib:R_0603_N [RESC1608N IPC]")
      (libsource (lib "PrometheusLib") (part "R_GENERIC_DIN"))
    )
    (comp (ref "R201")
      (value "100k")
      (footprint "PrometheusLib:R_0603_N [RESC1608N IPC]")
      (libsource (lib "PrometheusLib") (part "R_GENERIC_DIN"))
    )
    (comp (ref "R202")
      (value "523k")
      (footprint "PrometheusLib:R_0603_N [RESC1608N IPC]")
      (libsource (lib "PrometheusLib") (part "R_GENERIC_DIN"))
    )
    (comp (ref "R203")
      (value "100k")
      (footprint "PrometheusLib:R_0603_N [RESC1608N IPC]")
      (libsource (lib "PrometheusLib") (part "R_GENERIC_DIN"))
    )
    (comp (ref "R204")
      (value "100k")
      (footprint "PrometheusLib:R_0603_N [RESC1608N IPC]")
      (libsource (lib "PrometheusLib") (part "R_GENERIC_DIN"))
    )
    (comp (ref "R205")
      (value "100k")
      (footprint "PrometheusLib:R_0603_N [RESC1608N IPC]")
      (libsource (lib "PrometheusLib") (part "R_GENERIC_DIN"))
    )
    (comp (ref "R206")
      (value "150R")
      (footprint "PrometheusLib:R_0603_N [RESC1608N IPC]")
      (libsource (lib "PrometheusLib") (part "R_GENERIC_DIN"))
    )
    (comp (ref "R207")
      (value "560R")
      (footprint "PrometheusLib:R_0603_N [RESC1608N IPC]")
      (libsource (lib "") (part "R_GENERIC_DIN_2"))
    )
    (comp (ref "R208")
      (value "150R")
      (footprint "PrometheusLib:R_0603_N [RESC1608N IPC]")
      (libsource (lib "PrometheusLib") (part "R_GENERIC_DIN"))
    )
    (comp (ref "R209")
      (value "523k")
      (footprint "PrometheusLib:R_0603_N [RESC1608N IPC]")
      (libsource (lib "PrometheusLib") (part "R_GENERIC_DIN"))
    )
    (comp (ref "R210")
      (value "100k")
      (footprint "PrometheusLib:R_0603_N [RESC1608N IPC]")
      (libsource (lib "PrometheusLib") (part "R_GENERIC_DIN"))
    )
    (comp (ref "R211")
      (value "100k")
      (footprint "PrometheusLib:R_0603_N [RESC1608N IPC]")
      (libsource (lib "PrometheusLib") (part "R_GENERIC_DIN"))
    )
    (comp (ref "R212")
      (value "150R")
      (footprint "PrometheusLib:R_0603_N [RESC1608N IPC]")
      (libsource (lib "PrometheusLib") (part "R_GENERIC_DIN"))
    )
    (comp (ref "R213")
      (value "100k")
      (footprint "PrometheusLib:R_0603_N [RESC1608N IPC]")
      (libsource (lib "PrometheusLib") (part "R_GENERIC_DIN"))
    )
    (comp (ref "R214")
      (value "309k")
      (footprint "PrometheusLib:R_0603_N [RESC1608N IPC]")
      (libsource (lib "PrometheusLib") (part "R_GENERIC_DIN"))
    )
    (comp (ref "R215")
      (value "1K5")
      (footprint "PrometheusLib:R_0603_N [RESC1608N IPC]")
      (libsource (lib "") (part "R_GENERIC_DIN_1"))
    )
    (comp (ref "R216")
      (value "22K")
      (footprint "PrometheusLib:R_0603_N [RESC1608N IPC]")
      (libsource (lib "") (part "R_GENERIC_DIN_1"))
    )
    (comp (ref "R217")
      (value "100k")
      (footprint "PrometheusLib:R_0603_N [RESC1608N IPC]")
      (libsource (lib "PrometheusLib") (part "R_GENERIC_DIN"))
    )
    (comp (ref "R218")
      (value "68R")
      (footprint "PrometheusLib:R_0603_N [RESC1608N IPC]")
      (libsource (lib "PrometheusLib") (part "R_GENERIC_DIN"))
    )
    (comp (ref "TP200")
      (value "TP_GENERIC")
      (footprint "PrometheusLib:TP_0.8_P100T")
      (description "Needle Test Point")
      (libsource (lib "PrometheusLib") (part "TP_GENERIC"))
    )
    (comp (ref "TP201")
      (value "TP_GENERIC")
      (footprint "PrometheusLib:TP_0.8_P100T")
      (description "Needle Test Point")
      (libsource (lib "PrometheusLib") (part "TP_GENERIC"))
    )
    (comp (ref "TP202")
      (value "TP_GENERIC")
      (footprint "PrometheusLib:TP_0.8_P100T")
      (description "Needle Test Point")
      (libsource (lib "PrometheusLib") (part "TP_GENERIC"))
    )
    (comp (ref "TP203")
      (value "TP_GENERIC")
      (footprint "PrometheusLib:TP_0.8_P100T")
      (description "Needle Test Point")
      (libsource (lib "PrometheusLib") (part "TP_GENERIC"))
    )
    (comp (ref "TP204")
      (value "TP_GENERIC")
      (footprint "PrometheusLib:TP_0.8_P100T")
      (description "Needle Test Point")
      (libsource (lib "PrometheusLib") (part "TP_GENERIC"))
    )
    (comp (ref "TP205")
      (value "TP_GENERIC")
      (footprint "PrometheusLib:TP_0.8_P100T")
      (description "Needle Test Point")
      (libsource (lib "PrometheusLib") (part "TP_GENERIC"))
    )
    (comp (ref "TP206")
      (value "TP_GENERIC")
      (footprint "PrometheusLib:TP_0.8_P100T")
      (description "Needle Test Point")
      (libsource (lib "PrometheusLib") (part "TP_GENERIC"))
    )
    (comp (ref "TP207")
      (value "TP_GENERIC")
      (footprint "PrometheusLib:TP_0.8_P100T")
      (description "Needle Test Point")
      (libsource (lib "PrometheusLib") (part "TP_GENERIC"))
    )
    (comp (ref "TP208")
      (value "TP_GENERIC")
      (footprint "PrometheusLib:TP_0.8_P100T")
      (description "Needle Test Point")
      (libsource (lib "PrometheusLib") (part "TP_GENERIC"))
    )
    (comp (ref "TP209")
      (value "TP_GENERIC")
      (footprint "PrometheusLib:TP_0.8_P100T")
      (description "Needle Test Point")
      (libsource (lib "PrometheusLib") (part "TP_GENERIC"))
    )
    (comp (ref "TP210")
      (value "TP_GENERIC")
      (footprint "PrometheusLib:TP_0.8_P100T")
      (description "Needle Test Point")
      (libsource (lib "PrometheusLib") (part "TP_GENERIC"))
    )
    (comp (ref "TP211")
      (value "TP_GENERIC")
      (footprint "PrometheusLib:TP_0.8_P100T")
      (description "Needle Test Point")
      (libsource (lib "PrometheusLib") (part "TP_GENERIC"))
    )
    (comp (ref "TP212")
      (value "TP_GENERIC")
      (footprint "PrometheusLib:TP_0.8_P100T")
      (description "Needle Test Point")
      (libsource (lib "PrometheusLib") (part "TP_GENERIC"))
    )
    (comp (ref "TP213")
      (value "TP_GENERIC")
      (footprint "PrometheusLib:TP_0.8_P100T")
      (description "Needle Test Point")
      (libsource (lib "PrometheusLib") (part "TP_GENERIC"))
    )
  )
  (nets
    (net (code "3") (name "+12V") (class "Default")
      (node (ref "C220") (pin "1") (pintype "passive"))
      (node (ref "C221") (pin "1") (pintype "passive"))
      (node (ref "C222") (pin "1") (pintype "passive"))
      (node (ref "C226") (pin "1") (pintype "passive"))
      (node (ref "C227") (pin "1") (pintype "passive"))
      (node (ref "C228") (pin "1") (pintype "passive"))
      (node (ref "C232") (pin "1") (pintype "passive"))
      (node (ref "C233") (pin "1") (pintype "passive"))
      (node (ref "C234") (pin "1") (pintype "passive"))
      (node (ref "C235") (pin "1") (pintype "passive"))
      (node (ref "C236") (pin "1") (pintype "passive"))
      (node (ref "C237") (pin "1") (pintype "passive"))
      (node (ref "C238") (pin "1") (pintype "passive"))
      (node (ref "C239") (pin "1") (pintype "passive"))
      (node (ref "C240") (pin "1") (pintype "passive"))
      (node (ref "C241") (pin "1") (pintype "passive"))
      (node (ref "C242") (pin "1") (pintype "passive"))
      (node (ref "C243") (pin "1") (pintype "passive"))
      (node (ref "C244") (pin "1") (pintype "passive"))
      (node (ref "C275") (pin "1") (pintype "passive"))
      (node (ref "C276") (pin "1") (pintype "passive"))
      (node (ref "C277") (pin "1") (pintype "passive"))
      (node (ref "C332") (pin "1") (pintype "passive"))
      (node (ref "C333") (pin "1") (pintype "passive"))
      (node (ref "C334") (pin "1") (pintype "passive"))
      (node (ref "D202") (pin "A") (pinfunction "A_A") (pintype "passive"))
      (node (ref "FB200") (pin "2") (pintype "passive"))
      (node (ref "FB201") (pin "2") (pintype "passive"))
      (node (ref "FB204") (pin "2") (pintype "passive"))
      (node (ref "FB205") (pin "2") (pintype "passive"))
      (node (ref "IC201") (pin "15") (pinfunction "12V_15") (pintype "passive"))
      (node (ref "IC201") (pin "16") (pinfunction "12V_16") (pintype "passive"))
      (node (ref "R216") (pin "1") (pinfunction "1_1") (pintype "passive"))
      (node (ref "TP203") (pin "1") (pinfunction "1_1") (pintype "passive"))
    )
    (net (code "4") (name "/ADC_PG") (class "Default")
      (node (ref "IC205") (pin "5") (pinfunction "PWRGD_5") (pintype "open_collector"))
      (node (ref "TP209") (pin "1") (pinfunction "1_1") (pintype "passive"))
    )
    (net (code "5") (name "/A_PG") (class "Default")
      (node (ref "IC200") (pin "7") (pinfunction "PG_7") (pintype "open_collector"))
      (node (ref "IC205") (pin "8") (pinfunction "~{SD}_8") (pintype "passive"))
      (node (ref "R201") (pin "1") (pinfunction "1_1") (pintype "passive"))
      (node (ref "TP205") (pin "1") (pinfunction "1_1") (pintype "passive"))
    )
    (net (code "6") (name "/Analog EN") (class "Default")
      (node (ref "IC207") (pin "2") (pinfunction "Kathode_2") (pintype "passive"))
    )
    (net (code "7") (name "/EN_Phase3") (class "Default")
      (node (ref "IC203") (pin "8") (pinfunction "~{SD}_8") (pintype "passive"))
      (node (ref "IC204") (pin "1") (pinfunction "EN_1") (pintype "passive"))
      (node (ref "IC206") (pin "1") (pinfunction "EN_1") (pintype "passive"))
      (node (ref "TP210") (pin "1") (pinfunction "1_1") (pintype "passive"))
    )
    (net (code "8") (name "/IN12") (class "Default")
      (node (ref "IC201") (pin "1") (pinfunction "IN12_1") (pintype "passive"))
      (node (ref "IC201") (pin "2") (pinfunction "IN12_2") (pintype "passive"))
    )
    (net (code "9") (name "/IN36") (class "Default")
      (node (ref "IC201") (pin "3") (pinfunction "IN36_3") (pintype "passive"))
      (node (ref "IC201") (pin "4") (pinfunction "IN36_4") (pintype "passive"))
    )
    (net (code "10") (name "/IN45") (class "Default")
      (node (ref "IC201") (pin "5") (pinfunction "IN45_5") (pintype "passive"))
      (node (ref "IC201") (pin "6") (pinfunction "IN45_6") (pintype "passive"))
    )
    (net (code "11") (name "/IN78") (class "Default")
      (node (ref "IC201") (pin "7") (pinfunction "IN78_7") (pintype "passive"))
      (node (ref "IC201") (pin "8") (pinfunction "IN78_8") (pintype "passive"))
    )
    (net (code "12") (name "/PG_Phase2") (class "Default")
      (node (ref "IC202") (pin "7") (pinfunction "PG_7") (pintype "open_collector"))
      (node (ref "R210") (pin "1") (pinfunction "1_1") (pintype "passive"))
      (node (ref "TP208") (pin "1") (pinfunction "1_1") (pintype "passive"))
    )
    (net (code "13") (name "/PG_Phase3") (class "Default")
      (node (ref "IC203") (pin "5") (pinfunction "PWRGD_5") (pintype "open_collector"))
      (node (ref "IC204") (pin "7") (pinfunction "PG_7") (pintype "open_collector"))
      (node (ref "IC206") (pin "7") (pinfunction "PG_7") (pintype "open_collector"))
      (node (ref "R213") (pin "1") (pinfunction "1_1") (pintype "passive"))
      (node (ref "TP211") (pin "1") (pinfunction "1_1") (pintype "passive"))
    )
    (net (code "14") (name "/T2P#") (class "Default")
      (node (ref "IC201") (pin "10") (pinfunction "~{T2P}_10") (pintype "open_collector"))
      (node (ref "R205") (pin "1") (pinfunction "1_1") (pintype "passive"))
    )
    (net (code "15") (name "/VAUX") (class "Default")
      (node (ref "IC201") (pin "12") (pinfunction "VAUX_12") (pintype "passive"))
    )
    (net (code "16") (name "/VAUX_GND") (class "Default")
      (node (ref "IC201") (pin "11") (pinfunction "VAUX_GND_11") (pintype "passive"))
    )
    (net (code "17") (name "/Z_EN") (class "Default")
      (node (ref "IC200") (pin "1") (pinfunction "EN_1") (pintype "passive"))
      (node (ref "IC207") (pin "4") (pinfunction "Collector_4") (pintype "passive"))
      (node (ref "R216") (pin "2") (pinfunction "2_2") (pintype "passive"))
      (node (ref "TP213") (pin "1") (pinfunction "1_1") (pintype "passive"))
    )
    (net (code "19") (name "1V8_ADC") (class "Default")
      (node (ref "C284") (pin "1") (pintype "passive"))
      (node (ref "C285") (pin "1") (pintype "passive"))
      (node (ref "C286") (pin "1") (pintype "passive"))
      (node (ref "C307") (pin "1") (pintype "passive"))
      (node (ref "C308") (pin "1") (pintype "passive"))
      (node (ref "C309") (pin "1") (pintype "passive"))
      (node (ref "C310") (pin "1") (pintype "passive"))
      (node (ref "C311") (pin "1") (pintype "passive"))
      (node (ref "C312") (pin "1") (pintype "passive"))
      (node (ref "C313") (pin "1") (pintype "passive"))
      (node (ref "C314") (pin "1") (pintype "passive"))
      (node (ref "C315") (pin "1") (pintype "passive"))
      (node (ref "C316") (pin "1") (pintype "passive"))
      (node (ref "L204") (pin "3") (pinfunction "3_3") (pintype "passive"))
      (node (ref "TP207") (pin "1") (pinfunction "1_1") (pintype "passive"))
    )
    (net (code "20") (name "1V8_Con") (class "Default")
      (node (ref "C217") (pin "1") (pintype "passive"))
      (node (ref "C218") (pin "1") (pintype "passive"))
      (node (ref "C219") (pin "1") (pintype "passive"))
      (node (ref "C297") (pin "1") (pintype "passive"))
      (node (ref "C298") (pin "1") (pintype "passive"))
      (node (ref "C299") (pin "1") (pintype "passive"))
      (node (ref "C300") (pin "1") (pintype "passive"))
      (node (ref "C301") (pin "1") (pintype "passive"))
      (node (ref "C302") (pin "1") (pintype "passive"))
      (node (ref "C303") (pin "1") (pintype "passive"))
      (node (ref "C304") (pin "1") (pintype "passive"))
      (node (ref "C305") (pin "1") (pintype "passive"))
      (node (ref "C306") (pin "1") (pintype "passive"))
      (node (ref "FB203") (pin "1") (pintype "passive"))
      (node (ref "TP204") (pin "1") (pinfunction "1_1") (pintype "passive"))
    )
    (net (code "21") (name "3V3_Misc") (class "Default")
      (node (ref "C287") (pin "1") (pintype "passive"))
      (node (ref "C288") (pin "1") (pintype "passive"))
      (node (ref "C289") (pin "1") (pintype "passive"))
      (node (ref "C290") (pin "1") (pintype "passive"))
      (node (ref "C291") (pin "1") (pintype "passive"))
      (node (ref "C292") (pin "1") (pintype "passive"))
      (node (ref "C293") (pin "1") (pintype "passive"))
      (node (ref "C294") (pin "1") (pintype "passive"))
      (node (ref "C295") (pin "1") (pintype "passive"))
      (node (ref "C296") (pin "1") (pintype "passive"))
      (node (ref "C335") (pin "1") (pintype "passive"))
      (node (ref "C336") (pin "1") (pintype "passive"))
      (node (ref "C337") (pin "1") (pintype "passive"))
      (node (ref "D204") (pin "A") (pinfunction "A_A") (pintype "passive"))
      (node (ref "L205") (pin "3") (pinfunction "3_3") (pintype "passive"))
      (node (ref "R205") (pin "2") (pinfunction "2_2") (pintype "passive"))
      (node (ref "R213") (pin "2") (pinfunction "2_2") (pintype "passive"))
      (node (ref "R215") (pin "1") (pinfunction "1_1") (pintype "passive"))
      (node (ref "TP212") (pin "1") (pinfunction "1_1") (pintype "passive"))
    )
    (net (code "22") (name "5V_Amp") (class "Default")
      (node (ref "C223") (pin "1") (pintype "passive"))
      (node (ref "C224") (pin "1") (pintype "passive"))
      (node (ref "C225") (pin "1") (pintype "passive"))
      (node (ref "C322") (pin "1") (pintype "passive"))
      (node (ref "C323") (pin "1") (pintype "passive"))
      (node (ref "C324") (pin "1") (pintype "passive"))
      (node (ref "C325") (pin "1") (pintype "passive"))
      (node (ref "C326") (pin "1") (pintype "passive"))
      (node (ref "C327") (pin "1") (pintype "passive"))
      (node (ref "C328") (pin "1") (pintype "passive"))
      (node (ref "C329") (pin "1") (pintype "passive"))
      (node (ref "C330") (pin "1") (pintype "passive"))
      (node (ref "C331") (pin "1") (pintype "passive"))
      (node (ref "D200") (pin "A") (pinfunction "A_A") (pintype "passive"))
      (node (ref "L200") (pin "3") (pinfunction "3_3") (pintype "passive"))
      (node (ref "TP202") (pin "1") (pinfunction "1_1") (pintype "passive"))
    )
    (net (code "23") (name "5V_Analog") (class "Default")
      (node (ref "C206") (pin "1") (pintype "passive"))
      (node (ref "C207") (pin "1") (pintype "passive"))
      (node (ref "C281") (pin "1") (pintype "passive"))
      (node (ref "C282") (pin "1") (pintype "passive"))
      (node (ref "C283") (pin "1") (pintype "passive"))
      (node (ref "IC200") (pin "4") (pinfunction "Vout_4") (pintype "passive"))
      (node (ref "IC200") (pin "5") (pinfunction "Vout_5") (pintype "passive"))
      (node (ref "L200") (pin "2") (pinfunction "2_2") (pintype "passive"))
      (node (ref "L203") (pin "2") (pinfunction "2_2") (pintype "passive"))
      (node (ref "R200") (pin "2") (pinfunction "2_2") (pintype "passive"))
      (node (ref "R201") (pin "2") (pinfunction "2_2") (pintype "passive"))
      (node (ref "TP200") (pin "1") (pinfunction "1_1") (pintype "passive"))
    )
    (net (code "24") (name "5V_Zed") (class "Default")
      (node (ref "C214") (pin "1") (pintype "passive"))
      (node (ref "C215") (pin "1") (pintype "passive"))
      (node (ref "C216") (pin "1") (pintype "passive"))
      (node (ref "C229") (pin "1") (pintype "passive"))
      (node (ref "C230") (pin "1") (pintype "passive"))
      (node (ref "C231") (pin "1") (pintype "passive"))
      (node (ref "C250") (pin "1") (pintype "passive"))
      (node (ref "C251") (pin "1") (pintype "passive"))
      (node (ref "C252") (pin "1") (pintype "passive"))
      (node (ref "C253") (pin "1") (pintype "passive"))
      (node (ref "C254") (pin "1") (pintype "passive"))
      (node (ref "C255") (pin "1") (pintype "passive"))
      (node (ref "C256") (pin "1") (pintype "passive"))
      (node (ref "C257") (pin "1") (pintype "passive"))
      (node (ref "C258") (pin "1") (pintype "passive"))
      (node (ref "C259") (pin "1") (pintype "passive"))
      (node (ref "D201") (pin "A") (pinfunction "A_A") (pintype "passive"))
      (node (ref "FB202") (pin "2") (pintype "passive"))
      (node (ref "L201") (pin "3") (pinfunction "3_3") (pintype "passive"))
      (node (ref "R210") (pin "2") (pinfunction "2_2") (pintype "passive"))
      (node (ref "TP201") (pin "1") (pinfunction "1_1") (pintype "passive"))
    )
    (net (code "25") (name "ADC_GND") (class "Default")
      (node (ref "C284") (pin "2") (pintype "passive"))
      (node (ref "C285") (pin "2") (pintype "passive"))
      (node (ref "C286") (pin "2") (pintype "passive"))
      (node (ref "C307") (pin "2") (pintype "passive"))
      (node (ref "C308") (pin "2") (pintype "passive"))
      (node (ref "C309") (pin "2") (pintype "passive"))
      (node (ref "C310") (pin "2") (pintype "passive"))
      (node (ref "C311") (pin "2") (pintype "passive"))
      (node (ref "C312") (pin "2") (pintype "passive"))
      (node (ref "C313") (pin "2") (pintype "passive"))
      (node (ref "C314") (pin "2") (pintype "passive"))
      (node (ref "C315") (pin "2") (pintype "passive"))
      (node (ref "C316") (pin "2") (pintype "passive"))
      (node (ref "L204") (pin "2") (pinfunction "2_2") (pintype "passive"))
    )
    (net (code "26") (name "AmpGND") (class "Default")
      (node (ref "C223") (pin "2") (pintype "passive"))
      (node (ref "C224") (pin "2") (pintype "passive"))
      (node (ref "C225") (pin "2") (pintype "passive"))
      (node (ref "C322") (pin "2") (pintype "passive"))
      (node (ref "C323") (pin "2") (pintype "passive"))
      (node (ref "C324") (pin "2") (pintype "passive"))
      (node (ref "C325") (pin "2") (pintype "passive"))
      (node (ref "C326") (pin "2") (pintype "passive"))
      (node (ref "C327") (pin "2") (pintype "passive"))
      (node (ref "C328") (pin "2") (pintype "passive"))
      (node (ref "C329") (pin "2") (pintype "passive"))
      (node (ref "C330") (pin "2") (pintype "passive"))
      (node (ref "C331") (pin "2") (pintype "passive"))
      (node (ref "L200") (pin "4") (pinfunction "4_4") (pintype "passive"))
      (node (ref "R206") (pin "1") (pinfunction "1_1") (pintype "passive"))
    )
    (net (code "27") (name "Con_GND") (class "Default")
      (node (ref "C202") (pin "2") (pintype "passive"))
      (node (ref "C203") (pin "2") (pintype "passive"))
      (node (ref "C211") (pin "2") (pintype "passive"))
      (node (ref "C212") (pin "2") (pintype "passive"))
      (node (ref "C213") (pin "2") (pintype "passive"))
      (node (ref "C214") (pin "2") (pintype "passive"))
      (node (ref "C215") (pin "2") (pintype "passive"))
      (node (ref "C216") (pin "2") (pintype "passive"))
      (node (ref "C217") (pin "2") (pintype "passive"))
      (node (ref "C218") (pin "2") (pintype "passive"))
      (node (ref "C219") (pin "2") (pintype "passive"))
      (node (ref "C229") (pin "2") (pintype "passive"))
      (node (ref "C230") (pin "2") (pintype "passive"))
      (node (ref "C231") (pin "2") (pintype "passive"))
      (node (ref "C250") (pin "2") (pintype "passive"))
      (node (ref "C251") (pin "2") (pintype "passive"))
      (node (ref "C252") (pin "2") (pintype "passive"))
      (node (ref "C253") (pin "2") (pintype "passive"))
      (node (ref "C254") (pin "2") (pintype "passive"))
      (node (ref "C255") (pin "2") (pintype "passive"))
      (node (ref "C256") (pin "2") (pintype "passive"))
      (node (ref "C257") (pin "2") (pintype "passive"))
      (node (ref "C258") (pin "2") (pintype "passive"))
      (node (ref "C259") (pin "2") (pintype "passive"))
      (node (ref "C265") (pin "2") (pintype "passive"))
      (node (ref "C266") (pin "2") (pintype "passive"))
      (node (ref "C267") (pin "2") (pintype "passive"))
      (node (ref "C268") (pin "2") (pintype "passive"))
      (node (ref "C269") (pin "2") (pintype "passive"))
      (node (ref "C270") (pin "2") (pintype "passive"))
      (node (ref "C271") (pin "2") (pintype "passive"))
      (node (ref "C272") (pin "2") (pintype "passive"))
      (node (ref "C273") (pin "2") (pintype "passive"))
      (node (ref "C274") (pin "2") (pintype "passive"))
      (node (ref "C278") (pin "2") (pintype "passive"))
      (node (ref "C279") (pin "2") (pintype "passive"))
      (node (ref "C280") (pin "2") (pintype "passive"))
      (node (ref "C287") (pin "2") (pintype "passive"))
      (node (ref "C288") (pin "2") (pintype "passive"))
      (node (ref "C289") (pin "2") (pintype "passive"))
      (node (ref "C290") (pin "2") (pintype "passive"))
      (node (ref "C291") (pin "2") (pintype "passive"))
      (node (ref "C292") (pin "2") (pintype "passive"))
      (node (ref "C293") (pin "2") (pintype "passive"))
      (node (ref "C294") (pin "2") (pintype "passive"))
      (node (ref "C295") (pin "2") (pintype "passive"))
      (node (ref "C296") (pin "2") (pintype "passive"))
      (node (ref "C297") (pin "2") (pintype "passive"))
      (node (ref "C298") (pin "2") (pintype "passive"))
      (node (ref "C299") (pin "2") (pintype "passive"))
      (node (ref "C300") (pin "2") (pintype "passive"))
      (node (ref "C301") (pin "2") (pintype "passive"))
      (node (ref "C302") (pin "2") (pintype "passive"))
      (node (ref "C303") (pin "2") (pintype "passive"))
      (node (ref "C304") (pin "2") (pintype "passive"))
      (node (ref "C305") (pin "2") (pintype "passive"))
      (node (ref "C306") (pin "2") (pintype "passive"))
      (node (ref "C335") (pin "2") (pintype "passive"))
      (node (ref "C336") (pin "2") (pintype "passive"))
      (node (ref "C337") (pin "2") (pintype "passive"))
      (node (ref "IC201") (pin "9") (pinfunction "~{T2P}_GND_9") (pintype "passive"))
      (node (ref "IC203") (pin "11") (pinfunction "GND_11") (pintype "passive"))
      (node (ref "IC203") (pin "4") (pinfunction "GND_4") (pintype "passive"))
      (node (ref "L201") (pin "2") (pinfunction "2_2") (pintype "passive"))
      (node (ref "L202") (pin "2") (pinfunction "2_2") (pintype "passive"))
      (node (ref "L205") (pin "2") (pinfunction "2_2") (pintype "passive"))
      (node (ref "R208") (pin "1") (pinfunction "1_1") (pintype "passive"))
      (node (ref "R212") (pin "1") (pinfunction "1_1") (pintype "passive"))
      (node (ref "R218") (pin "1") (pinfunction "1_1") (pintype "passive"))
    )
    (net (code "28") (name "GND") (class "Default")
      (node (ref "C200") (pin "2") (pintype "passive"))
      (node (ref "C201") (pin "2") (pintype "passive"))
      (node (ref "C204") (pin "2") (pintype "passive"))
      (node (ref "C205") (pin "2") (pintype "passive"))
      (node (ref "C206") (pin "2") (pintype "passive"))
      (node (ref "C207") (pin "2") (pintype "passive"))
      (node (ref "C208") (pin "2") (pintype "passive"))
      (node (ref "C209") (pin "2") (pintype "passive"))
      (node (ref "C210") (pin "2") (pintype "passive"))
      (node (ref "C220") (pin "2") (pintype "passive"))
      (node (ref "C221") (pin "2") (pintype "passive"))
      (node (ref "C222") (pin "2") (pintype "passive"))
      (node (ref "C226") (pin "2") (pintype "passive"))
      (node (ref "C227") (pin "2") (pintype "passive"))
      (node (ref "C228") (pin "2") (pintype "passive"))
      (node (ref "C232") (pin "2") (pintype "passive"))
      (node (ref "C233") (pin "2") (pintype "passive"))
      (node (ref "C234") (pin "2") (pintype "passive"))
      (node (ref "C235") (pin "2") (pintype "passive"))
      (node (ref "C236") (pin "2") (pintype "passive"))
      (node (ref "C237") (pin "2") (pintype "passive"))
      (node (ref "C238") (pin "2") (pintype "passive"))
      (node (ref "C239") (pin "2") (pintype "passive"))
      (node (ref "C240") (pin "2") (pintype "passive"))
      (node (ref "C241") (pin "2") (pintype "passive"))
      (node (ref "C242") (pin "2") (pintype "passive"))
      (node (ref "C243") (pin "2") (pintype "passive"))
      (node (ref "C244") (pin "2") (pintype "passive"))
      (node (ref "C245") (pin "2") (pintype "passive"))
      (node (ref "C246") (pin "2") (pintype "passive"))
      (node (ref "C247") (pin "2") (pintype "passive"))
      (node (ref "C248") (pin "2") (pintype "passive"))
      (node (ref "C249") (pin "2") (pintype "passive"))
      (node (ref "C275") (pin "2") (pintype "passive"))
      (node (ref "C276") (pin "2") (pintype "passive"))
      (node (ref "C277") (pin "2") (pintype "passive"))
      (node (ref "C281") (pin "2") (pintype "passive"))
      (node (ref "C282") (pin "2") (pintype "passive"))
      (node (ref "C283") (pin "2") (pintype "passive"))
      (node (ref "C317") (pin "2") (pintype "passive"))
      (node (ref "C318") (pin "2") (pintype "passive"))
      (node (ref "C319") (pin "2") (pintype "passive"))
      (node (ref "C320") (pin "2") (pintype "passive"))
      (node (ref "C321") (pin "2") (pintype "passive"))
      (node (ref "C332") (pin "2") (pintype "passive"))
      (node (ref "C333") (pin "2") (pintype "passive"))
      (node (ref "C334") (pin "2") (pintype "passive"))
      (node (ref "IC200") (pin "3") (pinfunction "GND_3") (pintype "passive"))
      (node (ref "IC201") (pin "13") (pinfunction "0V_13") (pintype "passive"))
      (node (ref "IC201") (pin "14") (pinfunction "0V_14") (pintype "passive"))
      (node (ref "IC202") (pin "3") (pinfunction "GND_3") (pintype "passive"))
      (node (ref "IC204") (pin "3") (pinfunction "GND_3") (pintype "passive"))
      (node (ref "IC206") (pin "3") (pinfunction "GND_3") (pintype "passive"))
      (node (ref "IC207") (pin "3") (pinfunction "Emitter_3") (pintype "passive"))
      (node (ref "L200") (pin "1") (pinfunction "1_1") (pintype "passive"))
      (node (ref "L201") (pin "1") (pinfunction "1_1") (pintype "passive"))
      (node (ref "L202") (pin "1") (pinfunction "1_1") (pintype "passive"))
      (node (ref "L203") (pin "1") (pinfunction "1_1") (pintype "passive"))
      (node (ref "L205") (pin "1") (pinfunction "1_1") (pintype "passive"))
      (node (ref "R203") (pin "1") (pinfunction "1_1") (pintype "passive"))
      (node (ref "R204") (pin "1") (pinfunction "1_1") (pintype "passive"))
      (node (ref "R207") (pin "1") (pinfunction "1_1") (pintype "passive"))
      (node (ref "R211") (pin "1") (pinfunction "1_1") (pintype "passive"))
      (node (ref "R217") (pin "1") (pinfunction "1_1") (pintype "passive"))
    )
    (net (code "29") (name "Net-(C200-Pad1)") (class "Default")
      (node (ref "C200") (pin "1") (pintype "passive"))
      (node (ref "C201") (pin "1") (pintype "passive"))
      (node (ref "IC202") (pin "4") (pinfunction "Vout_4") (pintype "passive"))
      (node (ref "IC202") (pin "5") (pinfunction "Vout_5") (pintype "passive"))
      (node (ref "L201") (pin "4") (pinfunction "4_4") (pintype "passive"))
      (node (ref "R202") (pin "2") (pinfunction "2_2") (pintype "passive"))
    )
    (net (code "30") (name "Net-(C211-Pad1)") (class "Default")
      (node (ref "C211") (pin "1") (pintype "passive"))
      (node (ref "C212") (pin "1") (pintype "passive"))
      (node (ref "FB202") (pin "1") (pintype "passive"))
      (node (ref "IC203") (pin "10") (pinfunction "Vin_10") (pintype "passive"))
      (node (ref "IC203") (pin "9") (pinfunction "Vin_9") (pintype "passive"))
    )
    (net (code "31") (name "Net-(C245-Pad1)") (class "Default")
      (node (ref "C245") (pin "1") (pintype "passive"))
      (node (ref "C246") (pin "1") (pintype "passive"))
      (node (ref "IC204") (pin "4") (pinfunction "Vout_4") (pintype "passive"))
      (node (ref "IC204") (pin "5") (pinfunction "Vout_5") (pintype "passive"))
      (node (ref "L202") (pin "4") (pinfunction "4_4") (pintype "passive"))
      (node (ref "R209") (pin "2") (pinfunction "2_2") (pintype "passive"))
    )
    (net (code "32") (name "Net-(C260-Pad2)") (class "Default")
      (node (ref "C260") (pin "2") (pintype "passive"))
      (node (ref "C261") (pin "2") (pintype "passive"))
      (node (ref "C262") (pin "2") (pintype "passive"))
      (node (ref "C263") (pin "2") (pintype "passive"))
      (node (ref "C264") (pin "2") (pintype "passive"))
      (node (ref "IC205") (pin "11") (pinfunction "GND_11") (pintype "passive"))
      (node (ref "IC205") (pin "4") (pinfunction "GND_4") (pintype "passive"))
      (node (ref "L203") (pin "4") (pinfunction "4_4") (pintype "passive"))
      (node (ref "L204") (pin "1") (pinfunction "1_1") (pintype "passive"))
    )
    (net (code "33") (name "Net-(C263-Pad1)") (class "Default")
      (node (ref "C263") (pin "1") (pintype "passive"))
      (node (ref "C264") (pin "1") (pintype "passive"))
      (node (ref "IC205") (pin "10") (pinfunction "Vin_10") (pintype "passive"))
      (node (ref "IC205") (pin "9") (pinfunction "Vin_9") (pintype "passive"))
      (node (ref "L203") (pin "3") (pinfunction "3_3") (pintype "passive"))
    )
    (net (code "34") (name "Net-(C317-Pad1)") (class "Default")
      (node (ref "C317") (pin "1") (pintype "passive"))
      (node (ref "C318") (pin "1") (pintype "passive"))
      (node (ref "IC206") (pin "4") (pinfunction "Vout_4") (pintype "passive"))
      (node (ref "IC206") (pin "5") (pinfunction "Vout_5") (pintype "passive"))
      (node (ref "L205") (pin "4") (pinfunction "4_4") (pintype "passive"))
      (node (ref "R214") (pin "2") (pinfunction "2_2") (pintype "passive"))
    )
    (net (code "35") (name "Net-(D200-PadK)") (class "Default")
      (node (ref "D200") (pin "K") (pinfunction "K_K") (pintype "passive"))
      (node (ref "R206") (pin "2") (pinfunction "2_2") (pintype "passive"))
    )
    (net (code "36") (name "Net-(D201-PadK)") (class "Default")
      (node (ref "D201") (pin "K") (pinfunction "K_K") (pintype "passive"))
      (node (ref "R208") (pin "2") (pinfunction "2_2") (pintype "passive"))
    )
    (net (code "37") (name "Net-(D202-PadK)") (class "Default")
      (node (ref "D202") (pin "K") (pinfunction "K_K") (pintype "passive"))
      (node (ref "R207") (pin "2") (pinfunction "2_2") (pintype "passive"))
    )
    (net (code "38") (name "Net-(D203-PadK)") (class "Default")
      (node (ref "D203") (pin "K") (pinfunction "K_K") (pintype "passive"))
      (node (ref "R212") (pin "2") (pinfunction "2_2") (pintype "passive"))
    )
    (net (code "39") (name "Net-(D204-PadK)") (class "Default")
      (node (ref "D204") (pin "K") (pinfunction "K_K") (pintype "passive"))
      (node (ref "R218") (pin "2") (pinfunction "2_2") (pintype "passive"))
    )
    (net (code "40") (name "Net-(IC200-FB)") (class "Default")
      (node (ref "IC200") (pin "6") (pinfunction "FB_6") (pintype "passive"))
      (node (ref "R200") (pin "1") (pinfunction "1_1") (pintype "passive"))
      (node (ref "R203") (pin "2") (pinfunction "2_2") (pintype "passive"))
    )
    (net (code "41") (name "Net-(IC200-SS{slash}TR)") (class "Default")
      (node (ref "C205") (pin "1") (pintype "passive"))
      (node (ref "IC200") (pin "8") (pinfunction "SS/TR_8") (pintype "passive"))
    )
    (net (code "42") (name "Net-(IC200-Vin)") (class "Default")
      (node (ref "C204") (pin "1") (pintype "passive"))
      (node (ref "FB200") (pin "1") (pintype "passive"))
      (node (ref "IC200") (pin "2") (pinfunction "Vin_2") (pintype "passive"))
    )
    (net (code "43") (name "Net-(IC202-EN)") (class "Default")
      (node (ref "C208") (pin "1") (pintype "passive"))
      (node (ref "C209") (pin "1") (pintype "passive"))
      (node (ref "FB201") (pin "1") (pintype "passive"))
      (node (ref "IC202") (pin "1") (pinfunction "EN_1") (pintype "passive"))
      (node (ref "IC202") (pin "2") (pinfunction "Vin_2") (pintype "passive"))
    )
    (net (code "44") (name "Net-(IC202-FB)") (class "Default")
      (node (ref "IC202") (pin "6") (pinfunction "FB_6") (pintype "passive"))
      (node (ref "R202") (pin "1") (pinfunction "1_1") (pintype "passive"))
      (node (ref "R204") (pin "2") (pinfunction "2_2") (pintype "passive"))
    )
    (net (code "45") (name "Net-(IC202-SS{slash}TR)") (class "Default")
      (node (ref "C210") (pin "1") (pintype "passive"))
      (node (ref "IC202") (pin "8") (pinfunction "SS/TR_8") (pintype "passive"))
    )
    (net (code "46") (name "Net-(IC203-NR)") (class "Default")
      (node (ref "C213") (pin "1") (pintype "passive"))
      (node (ref "IC203") (pin "7") (pinfunction "NR_7") (pintype "passive"))
    )
    (net (code "47") (name "Net-(IC203-Sense{slash}Adj)") (class "Default")
      (node (ref "C202") (pin "1") (pintype "passive"))
      (node (ref "C203") (pin "1") (pintype "passive"))
      (node (ref "FB203") (pin "2") (pintype "passive"))
      (node (ref "IC203") (pin "1") (pinfunction "Vout_1") (pintype "passive"))
      (node (ref "IC203") (pin "2") (pinfunction "Vout_2") (pintype "passive"))
      (node (ref "IC203") (pin "3") (pinfunction "Sense/Adj_3") (pintype "passive"))
    )
    (net (code "48") (name "Net-(IC204-FB)") (class "Default")
      (node (ref "IC204") (pin "6") (pinfunction "FB_6") (pintype "passive"))
      (node (ref "R209") (pin "1") (pinfunction "1_1") (pintype "passive"))
      (node (ref "R211") (pin "2") (pinfunction "2_2") (pintype "passive"))
    )
    (net (code "49") (name "Net-(IC204-SS{slash}TR)") (class "Default")
      (node (ref "C249") (pin "1") (pintype "passive"))
      (node (ref "IC204") (pin "8") (pinfunction "SS/TR_8") (pintype "passive"))
    )
    (net (code "50") (name "Net-(IC204-Vin)") (class "Default")
      (node (ref "C247") (pin "1") (pintype "passive"))
      (node (ref "C248") (pin "1") (pintype "passive"))
      (node (ref "FB204") (pin "1") (pintype "passive"))
      (node (ref "IC204") (pin "2") (pinfunction "Vin_2") (pintype "passive"))
    )
    (net (code "51") (name "Net-(IC205-NR)") (class "Default")
      (node (ref "C260") (pin "1") (pintype "passive"))
      (node (ref "IC205") (pin "7") (pinfunction "NR_7") (pintype "passive"))
    )
    (net (code "52") (name "Net-(IC205-Sense{slash}Adj)") (class "Default")
      (node (ref "C261") (pin "1") (pintype "passive"))
      (node (ref "C262") (pin "1") (pintype "passive"))
      (node (ref "IC205") (pin "1") (pinfunction "Vout_1") (pintype "passive"))
      (node (ref "IC205") (pin "2") (pinfunction "Vout_2") (pintype "passive"))
      (node (ref "IC205") (pin "3") (pinfunction "Sense/Adj_3") (pintype "passive"))
      (node (ref "L204") (pin "4") (pinfunction "4_4") (pintype "passive"))
    )
    (net (code "53") (name "Net-(IC206-FB)") (class "Default")
      (node (ref "IC206") (pin "6") (pinfunction "FB_6") (pintype "passive"))
      (node (ref "R214") (pin "1") (pinfunction "1_1") (pintype "passive"))
      (node (ref "R217") (pin "2") (pinfunction "2_2") (pintype "passive"))
    )
    (net (code "54") (name "Net-(IC206-SS{slash}TR)") (class "Default")
      (node (ref "C321") (pin "1") (pintype "passive"))
      (node (ref "IC206") (pin "8") (pinfunction "SS/TR_8") (pintype "passive"))
    )
    (net (code "55") (name "Net-(IC206-Vin)") (class "Default")
      (node (ref "C319") (pin "1") (pintype "passive"))
      (node (ref "C320") (pin "1") (pintype "passive"))
      (node (ref "FB205") (pin "1") (pintype "passive"))
      (node (ref "IC206") (pin "2") (pinfunction "Vin_2") (pintype "passive"))
    )
    (net (code "56") (name "Net-(IC207-Anode)") (class "Default")
      (node (ref "IC207") (pin "1") (pinfunction "Anode_1") (pintype "passive"))
      (node (ref "R215") (pin "2") (pinfunction "2_2") (pintype "passive"))
    )
    (net (code "57") (name "USB_VBUS") (class "Default")
      (node (ref "C265") (pin "1") (pintype "passive"))
      (node (ref "C266") (pin "1") (pintype "passive"))
      (node (ref "C267") (pin "1") (pintype "passive"))
      (node (ref "C268") (pin "1") (pintype "passive"))
      (node (ref "C269") (pin "1") (pintype "passive"))
      (node (ref "C270") (pin "1") (pintype "passive"))
      (node (ref "C271") (pin "1") (pintype "passive"))
      (node (ref "C272") (pin "1") (pintype "passive"))
      (node (ref "C273") (pin "1") (pintype "passive"))
      (node (ref "C274") (pin "1") (pintype "passive"))
      (node (ref "C278") (pin "1") (pintype "passive"))
      (node (ref "C279") (pin "1") (pintype "passive"))
      (node (ref "C280") (pin "1") (pintype "passive"))
      (node (ref "D203") (pin "A") (pinfunction "A_A") (pintype "passive"))
      (node (ref "L202") (pin "3") (pinfunction "3_3") (pintype "passive"))
      (node (ref "TP206") (pin "1") (pinfunction "1_1") (pintype "passive"))
    )
  )
)
